# pwr.net
KiCad netlist of a schematic drawn in EAGLE
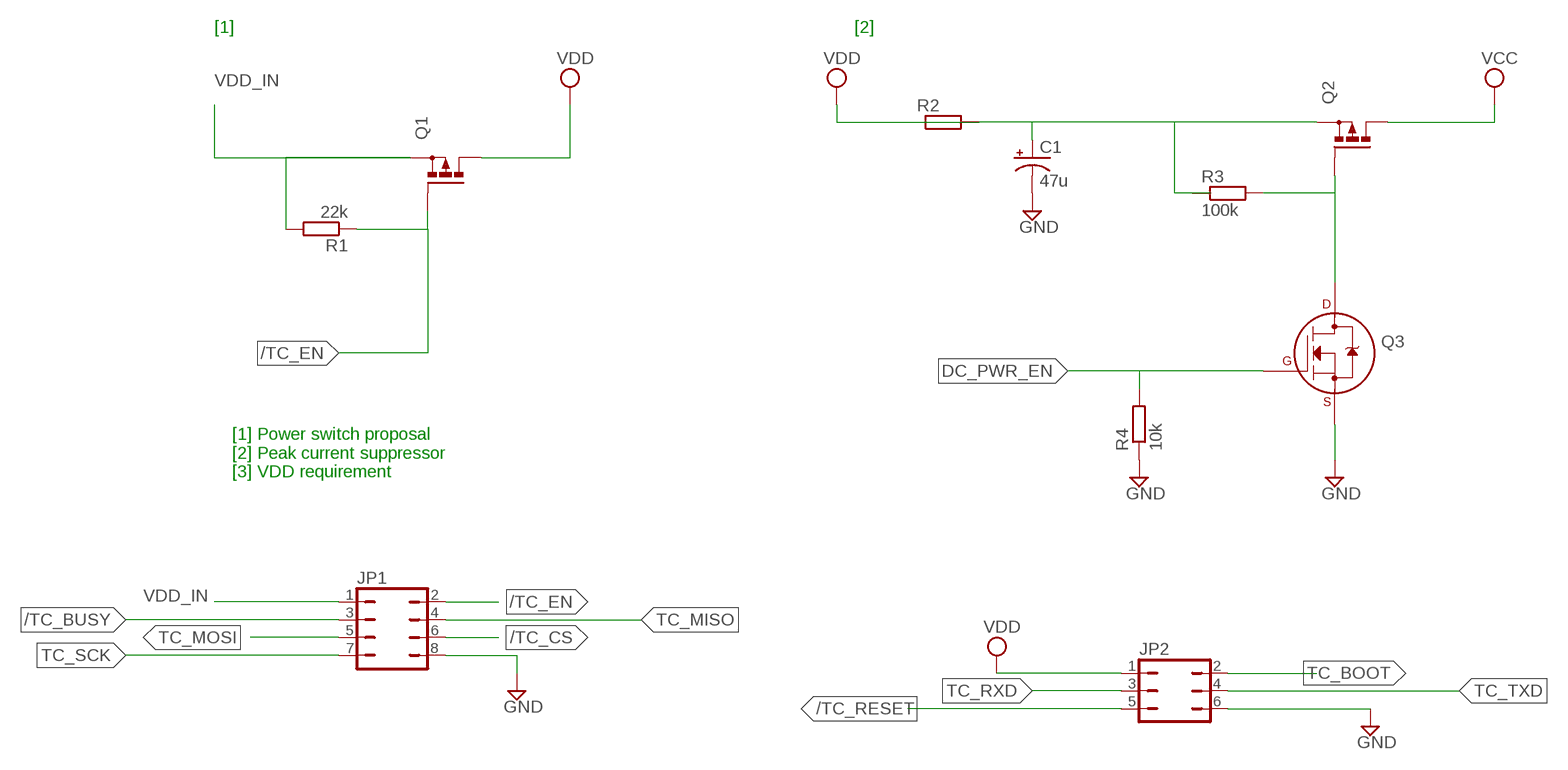
[diagram p0: schematic, sheet 1]

(export (version "E")
  (design (tool "Eeschema 10.0.6"))
  (components
    (comp (ref "C1")
      (value "47u")
      (footprint "eagle-import:B_3528-21R")
      (libsource (lib "eagle-import") (part "CPOL-USB/3528-21R"))
    )
    (comp (ref "JP1")
      (value "JP4Q")
      (footprint "eagle-import:JP4Q")
      (libsource (lib "eagle-import") (part "JP4Q"))
    )
    (comp (ref "JP2")
      (value "JP3Q")
      (footprint "eagle-import:JP3Q")
      (libsource (lib "eagle-import") (part "JP3Q"))
    )
    (comp (ref "Q1")
      (value "NTR4171PTG")
      (footprint "eagle-import:SOT23")
      (libsource (lib "eagle-import") (part "NTR4171PTG"))
    )
    (comp (ref "Q2")
      (value "NTR4171PTG")
      (footprint "eagle-import:SOT23")
      (libsource (lib "eagle-import") (part "NTR4171PTG"))
    )
    (comp (ref "Q3")
      (value "2N7002_SOT23")
      (footprint "eagle-import:SOT-23")
      (libsource (lib "eagle-import") (part "2N700_SOT232"))
    )
    (comp (ref "R1")
      (value "22k")
      (footprint "eagle-import:R0603")
      (libsource (lib "eagle-import") (part "resistor_R-EU_R0603"))
    )
    (comp (ref "R2")
      (value "R-EU_R0603")
      (footprint "eagle-import:R0603")
      (libsource (lib "eagle-import") (part "R-EU_R0603"))
    )
    (comp (ref "R3")
      (value "100k")
      (footprint "eagle-import:R0603")
      (libsource (lib "eagle-import") (part "R-EU_R0603"))
    )
    (comp (ref "R4")
      (value "10k")
      (footprint "eagle-import:R0603")
      (libsource (lib "eagle-import") (part "R-EU_R0603"))
    )
  )
  (nets
    (net (code "1") (name "/VDD_IN") (class "Default")
      (node (ref "JP1") (pin "1") (pinfunction "1_1") (pintype "passive"))
      (node (ref "Q1") (pin "S") (pinfunction "S_S") (pintype "passive"))
      (node (ref "R1") (pin "2") (pinfunction "2_2") (pintype "passive"))
    )
    (net (code "2") (name "DC_PWR_EN") (class "Default")
      (node (ref "Q3") (pin "1") (pinfunction "G_1") (pintype "tri_state"))
      (node (ref "R4") (pin "2") (pinfunction "2_2") (pintype "passive"))
    )
    (net (code "3") (name "GND") (class "Default")
      (node (ref "C1") (pin "-") (pinfunction "-_-") (pintype "passive"))
      (node (ref "JP1") (pin "8") (pinfunction "8_8") (pintype "passive"))
      (node (ref "JP2") (pin "6") (pinfunction "6_6") (pintype "passive"))
      (node (ref "Q3") (pin "2") (pinfunction "S_2") (pintype "bidirectional"))
      (node (ref "R4") (pin "1") (pinfunction "1_1") (pintype "passive"))
    )
    (net (code "4") (name "Net-(Q3-D)") (class "Default")
      (node (ref "Q2") (pin "G") (pinfunction "G_G") (pintype "passive"))
      (node (ref "Q3") (pin "3") (pinfunction "D_3") (pintype "bidirectional"))
      (node (ref "R3") (pin "2") (pinfunction "2_2") (pintype "passive"))
    )
    (net (code "5") (name "TC_BOOT") (class "Default")
      (node (ref "JP2") (pin "2") (pinfunction "2_2") (pintype "passive"))
    )
    (net (code "6") (name "TC_MISO") (class "Default")
      (node (ref "JP1") (pin "4") (pinfunction "4_4") (pintype "passive"))
    )
    (net (code "7") (name "TC_MOSI") (class "Default")
      (node (ref "JP1") (pin "5") (pinfunction "5_5") (pintype "passive"))
    )
    (net (code "8") (name "TC_RXD") (class "Default")
      (node (ref "JP2") (pin "3") (pinfunction "3_3") (pintype "passive"))
    )
    (net (code "9") (name "TC_SCK") (class "Default")
      (node (ref "JP1") (pin "7") (pinfunction "7_7") (pintype "passive"))
    )
    (net (code "10") (name "TC_TXD") (class "Default")
      (node (ref "JP2") (pin "4") (pinfunction "4_4") (pintype "passive"))
    )
    (net (code "11") (name "VCC") (class "Default")
      (node (ref "Q2") (pin "D") (pinfunction "D_D") (pintype "passive"))
    )
    (net (code "12") (name "VDD") (class "Default")
      (node (ref "C1") (pin "+") (pinfunction "+_+") (pintype "passive"))
      (node (ref "JP2") (pin "1") (pinfunction "1_1") (pintype "passive"))
      (node (ref "Q1") (pin "D") (pinfunction "D_D") (pintype "passive"))
      (node (ref "Q2") (pin "S") (pinfunction "S_S") (pintype "passive"))
      (node (ref "R2") (pin "1") (pinfunction "1_1") (pintype "passive"))
      (node (ref "R2") (pin "2") (pinfunction "2_2") (pintype "passive"))
    )
    (net (code "13") (name "unconnected-(R3-Pad1)") (class "Default")
      (node (ref "R3") (pin "1") (pinfunction "1_1") (pintype "passive"))
    )
    (net (code "14") (name "{slash}TC_BUSY") (class "Default")
      (node (ref "JP1") (pin "3") (pinfunction "3_3") (pintype "passive"))
    )
    (net (code "15") (name "{slash}TC_CS") (class "Default")
      (node (ref "JP1") (pin "6") (pinfunction "6_6") (pintype "passive"))
    )
    (net (code "16") (name "{slash}TC_EN") (class "Default")
      (node (ref "JP1") (pin "2") (pinfunction "2_2") (pintype "passive"))
      (node (ref "Q1") (pin "G") (pinfunction "G_G") (pintype "passive"))
      (node (ref "R1") (pin "1") (pinfunction "1_1") (pintype "passive"))
    )
    (net (code "17") (name "{slash}TC_RESET") (class "Default")
      (node (ref "JP2") (pin "5") (pinfunction "5_5") (pintype "passive"))
    )
  )
)
